# Driver_MOSFET_DC_Input.net
KiCad netlist of a schematic drawn in Altium Designer
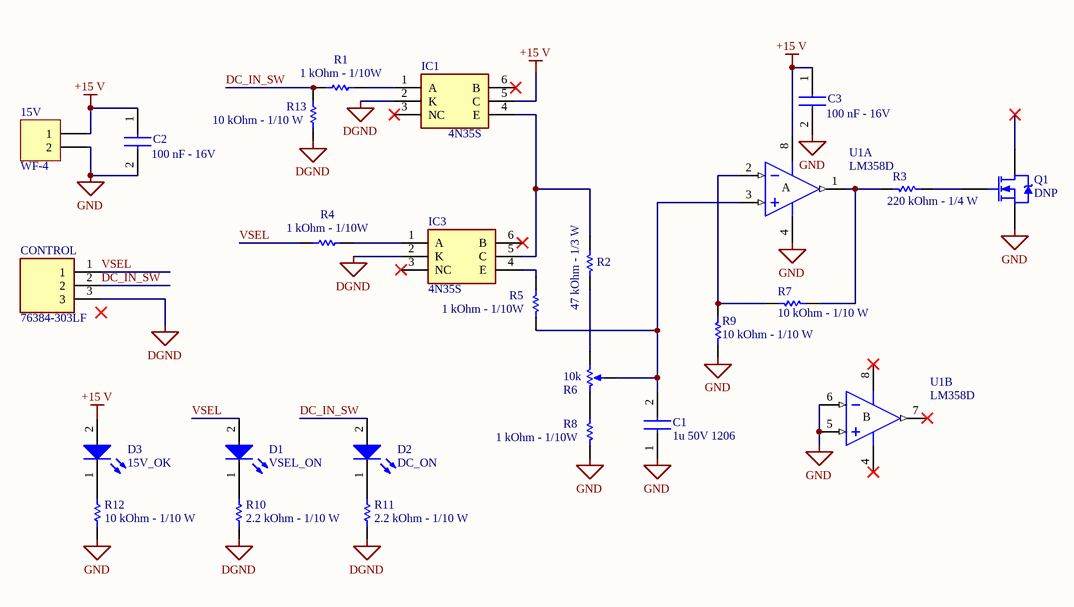
[diagram p0: Driver_MOSFET_DC_Input.SchDoc]

(export (version "E")
  (design (tool "Eeschema 10.0.6"))
  (components
    (comp (ref "15V")
      (value "WF-4")
      (footprint "HDR1X2")
      (description "Header, 2-Pin")
      (fields
        (field (name "MANUFACTURER_PART_NUMBER") "Header 2P")
        (field (name "PUBLISHER") "Altium Limited")
      )
      (libsource (lib "Miscellaneous Connectors") (part "MHDR1X2"))
    )
    (comp (ref "C1")
      (value "1u 50V 1206")
      (footprint "SamacSys:CAPC3216X180N")
      (description "Capacitor")
      (fields
        (field (name "MANUFACTURER_PART_NUMBER") "C3216X7R1H105K160AE")
        (field (name "MOUSER PART NUMBER") "810-C3216X7R1H105KST")
      )
      (libsource (lib "*") (part "C3216X7R1H105K160AE"))
    )
    (comp (ref "C2")
      (value "100 nF - 16V")
      (footprint "CAPC1608X95N")
      (description "Capacitor")
      (fields
        (field (name "MANUFACTURER_PART_NUMBER") "EMK107B7104KA-T")
        (field (name "MOUSER PART NUMBER") "963-EMK107B7104KA-T")
      )
      (libsource (lib "SamacSys") (part "EMK107B7104KA-T"))
    )
    (comp (ref "C3")
      (value "100 nF - 16V")
      (footprint "CAPC1608X95N")
      (description "Capacitor")
      (fields
        (field (name "MANUFACTURER_PART_NUMBER") "EMK107B7104KA-T")
        (field (name "MOUSER PART NUMBER") "963-EMK107B7104KA-T")
      )
      (libsource (lib "SamacSys") (part "EMK107B7104KA-T"))
    )
    (comp (ref "CONTROL")
      (value "76384-303LF")
      (footprint "76384303LF")
      (description "Connector")
      (fields (field (name "MOUSER PART NUMBER") "649-76384-303LF"))
      (libsource (lib "SamacSys") (part "76384-303LF"))
    )
    (comp (ref "D1")
      (value "VSEL_ON")
      (footprint "SamacSys:LEDC1608X80N")
      (description "LED")
      (fields
        (field (name "MANUFACTURER_PART_NUMBER") "150060GS75000")
        (field (name "MOUSER PART NUMBER") "710-150060GS75000")
      )
      (libsource (lib "SamacSys") (part "150060GS75000"))
    )
    (comp (ref "D2")
      (value "DC_ON")
      (footprint "SamacSys:LEDC1608X80N")
      (description "LED")
      (fields
        (field (name "MANUFACTURER_PART_NUMBER") "150060GS75000")
        (field (name "MOUSER PART NUMBER") "710-150060GS75000")
      )
      (libsource (lib "SamacSys") (part "150060GS75000"))
    )
    (comp (ref "D3")
      (value "15V_OK")
      (footprint "SamacSys:LEDC1608X80N")
      (description "LED")
      (fields
        (field (name "MANUFACTURER_PART_NUMBER") "150060GS75000")
        (field (name "MOUSER PART NUMBER") "710-150060GS75000")
      )
      (libsource (lib "SamacSys") (part "150060GS75000"))
    )
    (comp (ref "IC1")
      (value "4N35S")
      (footprint "SamacSys:4N35S")
      (description "Integrated Circuit")
      (libsource (lib "SamacSys") (part "4N35S"))
    )
    (comp (ref "IC3")
      (value "4N35S")
      (footprint "SamacSys:4N35S")
      (description "Integrated Circuit")
      (libsource (lib "SamacSys") (part "4N35S"))
    )
    (comp (ref "Q1")
      (value "DNP")
      (footprint "TO-247 Horiz. Heatsink")
      (description "Infineon Power MOSFET N-Channel 650V 31.2A")
      (fields (field (name "PUBLISHER") "Altium Limited"))
      (libsource (lib "MOSFET") (part "IPx65R110CFD"))
    )
    (comp (ref "R1")
      (value "1 kOhm - 1/10W")
      (footprint "SamacSys:RESC1608X55N")
      (description "Resistor")
      (fields (field (name "MANUFACTURER_PART_NUMBER") "RMC16K102FTP") (field (name "Comment") "1k"))
      (libsource (lib "SamacSys") (part "RMC16K102FTP"))
    )
    (comp (ref "R2")
      (value "47 kOhm - 1/3 W")
      (footprint "RESC1608X55N")
      (description "Resistor")
      (fields
        (field (name "MANUFACTURER_PART_NUMBER") "CRCW060347K0FKEAHP")
        (field (name "Comment") "Res1")
        (field (name "PUBLISHER") "Altium Limited")
      )
      (libsource (lib "Miscellaneous Devices") (part "Res1"))
    )
    (comp (ref "R3")
      (value "220 kOhm - 1/4 W")
      (footprint "RESC1608X55N")
      (description "Resistor")
      (fields
        (field (name "MANUFACTURER_PART_NUMBER") "CRCW1206220KFKEA")
        (field (name "Comment") "Res1")
        (field (name "PUBLISHER") "Altium Limited")
      )
      (libsource (lib "Miscellaneous Devices") (part "Res1"))
    )
    (comp (ref "R4")
      (value "1 kOhm - 1/10W")
      (footprint "SamacSys:RESC1608X55N")
      (description "Resistor")
      (fields (field (name "MANUFACTURER_PART_NUMBER") "RMC16K102FTP") (field (name "Comment") "1k"))
      (libsource (lib "SamacSys") (part "RMC16K102FTP"))
    )
    (comp (ref "R5")
      (value "1 kOhm - 1/10W")
      (footprint "RESC1608X55N")
      (description "Resistor")
      (fields
        (field (name "MANUFACTURER_PART_NUMBER") "RMC16K102FTP")
        (field (name "Comment") "Res1")
        (field (name "PUBLISHER") "Altium Limited")
      )
      (libsource (lib "Miscellaneous Devices") (part "Res1"))
    )
    (comp (ref "R6")
      (value "10k")
      (footprint "SamacSys:3296W-1")
      (description "Resistor")
      (fields
        (field (name "MANUFACTURER_PART_NUMBER") "3296W-1-502LF")
        (field (name "MOUSER PART NUMBER") "652-3296W-1-502LF")
      )
      (libsource (lib "SamacSys") (part "3296W-1-502LF"))
    )
    (comp (ref "R7")
      (value "10 kOhm - 1/10 W")
      (footprint "RESC1608X55N")
      (description "Resistor")
      (fields
        (field (name "MANUFACTURER_PART_NUMBER") "CRCW060310K0FKEA")
        (field (name "Comment") "Res1")
        (field (name "PUBLISHER") "Altium Limited")
      )
      (libsource (lib "Miscellaneous Devices") (part "Res1"))
    )
    (comp (ref "R8")
      (value "1 kOhm - 1/10W")
      (footprint "RESC1608X55N")
      (description "Resistor")
      (fields
        (field (name "MANUFACTURER_PART_NUMBER") "RMC16K102FTP")
        (field (name "Comment") "Res1")
        (field (name "PUBLISHER") "Altium Limited")
      )
      (libsource (lib "Miscellaneous Devices") (part "Res1"))
    )
    (comp (ref "R9")
      (value "10 kOhm - 1/10 W")
      (footprint "RESC1608X55N")
      (description "Resistor")
      (fields
        (field (name "MANUFACTURER_PART_NUMBER") "CRCW060310K0FKEA")
        (field (name "Comment") "Res1")
        (field (name "PUBLISHER") "Altium Limited")
      )
      (libsource (lib "Miscellaneous Devices") (part "Res1"))
    )
    (comp (ref "R10")
      (value "2.2 kOhm - 1/10 W")
      (footprint "RESC1608X50N")
      (description "Resistor")
      (fields
        (field (name "MANUFACTURER_PART_NUMBER") "CRCW06032K20FKEA")
        (field (name "MOUSER PART NUMBER") "71-CRCW0603-2.2K-E3")
      )
      (libsource (lib "SamacSys") (part "CRCW06032K20FKEA"))
    )
    (comp (ref "R11")
      (value "2.2 kOhm - 1/10 W")
      (footprint "RESC1608X50N")
      (description "Resistor")
      (fields
        (field (name "MANUFACTURER_PART_NUMBER") "CRCW06032K20FKEA")
        (field (name "MOUSER PART NUMBER") "71-CRCW0603-2.2K-E3")
      )
      (libsource (lib "SamacSys") (part "CRCW06032K20FKEA"))
    )
    (comp (ref "R12")
      (value "10 kOhm - 1/10 W")
      (footprint "RESC1608X50N")
      (description "Resistor")
      (fields
        (field (name "MANUFACTURER_PART_NUMBER") "CRCW060310K0FKEA")
        (field (name "MOUSER PART NUMBER") "71-CRCW0603-10K-E3")
      )
      (libsource (lib "SamacSys") (part "CRCW060310K0FKEA"))
    )
    (comp (ref "R13")
      (value "10 kOhm - 1/10 W")
      (footprint "RESC1608X50N")
      (description "Resistor")
      (fields
        (field (name "MANUFACTURER_PART_NUMBER") "CRCW060310K0FKEA")
        (field (name "MOUSER PART NUMBER") "71-CRCW0603-10K-E3")
      )
      (libsource (lib "SamacSys") (part "CRCW060310K0FKEA"))
    )
    (comp (ref "U1")
      (value "LM358D")
      (footprint "751-07_M")
      (description "Dual Operational Amplifier")
      (fields
        (field (name "MANUFACTURER_PART_NUMBER") "LM358AM/NOPB")
        (field (name "PUBLISHER") "Altium Limited")
      )
      (libsource (lib "TI Operational Amplifier") (part "LM358D"))
    )
  )
  (nets
    (net (code "1") (name "+15 V") (class "Default")
      (node (ref "15V") (pin "1") (pinfunction "1_1") (pintype "passive"))
      (node (ref "C2") (pin "1") (pinfunction "1_1") (pintype "passive"))
      (node (ref "C3") (pin "1") (pinfunction "1_1") (pintype "passive"))
      (node (ref "D3") (pin "2") (pinfunction "A_2") (pintype "passive"))
      (node (ref "IC1") (pin "5") (pinfunction "C_5") (pintype "passive"))
      (node (ref "U1") (pin "8") (pinfunction "V+_8") (pintype "power_in"))
    )
    (net (code "2") (name "/DC_IN_SW") (class "Default")
      (node (ref "CONTROL") (pin "2") (pinfunction "2_2") (pintype "passive"))
      (node (ref "D2") (pin "2") (pinfunction "A_2") (pintype "passive"))
      (node (ref "R1") (pin "1") (pinfunction "1_1") (pintype "passive"))
      (node (ref "R13") (pin "2") (pinfunction "2_2") (pintype "passive"))
    )
    (net (code "3") (name "/VSEL") (class "Default")
      (node (ref "CONTROL") (pin "1") (pinfunction "1_1") (pintype "passive"))
      (node (ref "D1") (pin "2") (pinfunction "A_2") (pintype "passive"))
      (node (ref "R4") (pin "1") (pinfunction "1_1") (pintype "passive"))
    )
    (net (code "4") (name "DGND") (class "Default")
      (node (ref "CONTROL") (pin "3") (pinfunction "3_3") (pintype "passive"))
      (node (ref "IC1") (pin "2") (pinfunction "K_2") (pintype "passive"))
      (node (ref "IC3") (pin "2") (pinfunction "K_2") (pintype "passive"))
      (node (ref "R10") (pin "1") (pinfunction "1_1") (pintype "passive"))
      (node (ref "R11") (pin "1") (pinfunction "1_1") (pintype "passive"))
      (node (ref "R13") (pin "1") (pinfunction "1_1") (pintype "passive"))
    )
    (net (code "5") (name "GND") (class "Default")
      (node (ref "15V") (pin "2") (pinfunction "2_2") (pintype "passive"))
      (node (ref "C1") (pin "1") (pinfunction "1_1") (pintype "passive"))
      (node (ref "C2") (pin "2") (pinfunction "2_2") (pintype "passive"))
      (node (ref "C3") (pin "2") (pinfunction "2_2") (pintype "passive"))
      (node (ref "Q1") (pin "3") (pinfunction "S_3") (pintype "passive"))
      (node (ref "R12") (pin "1") (pinfunction "1_1") (pintype "passive"))
      (node (ref "R8") (pin "2") (pinfunction "2_2") (pintype "passive"))
      (node (ref "R9") (pin "2") (pinfunction "2_2") (pintype "passive"))
      (node (ref "U1") (pin "4") (pinfunction "V-_4") (pintype "power_in"))
      (node (ref "U1") (pin "5") (pinfunction "IN+_5") (pintype "input"))
      (node (ref "U1") (pin "6") (pinfunction "IN-_6") (pintype "input"))
    )
    (net (code "6") (name "Net-(D1-K)") (class "Default")
      (node (ref "D1") (pin "1") (pinfunction "K_1") (pintype "passive"))
      (node (ref "R10") (pin "2") (pinfunction "2_2") (pintype "passive"))
    )
    (net (code "7") (name "Net-(D2-K)") (class "Default")
      (node (ref "D2") (pin "1") (pinfunction "K_1") (pintype "passive"))
      (node (ref "R11") (pin "2") (pinfunction "2_2") (pintype "passive"))
    )
    (net (code "8") (name "Net-(D3-K)") (class "Default")
      (node (ref "D3") (pin "1") (pinfunction "K_1") (pintype "passive"))
      (node (ref "R12") (pin "2") (pinfunction "2_2") (pintype "passive"))
    )
    (net (code "9") (name "Net-(IC1-A)") (class "Default")
      (node (ref "IC1") (pin "1") (pinfunction "A_1") (pintype "passive"))
      (node (ref "R1") (pin "2") (pinfunction "2_2") (pintype "passive"))
    )
    (net (code "10") (name "Net-(IC1-E)") (class "Default")
      (node (ref "IC1") (pin "4") (pinfunction "E_4") (pintype "passive"))
      (node (ref "IC3") (pin "5") (pinfunction "C_5") (pintype "passive"))
      (node (ref "R2") (pin "1") (pinfunction "1_1") (pintype "passive"))
    )
    (net (code "11") (name "Net-(IC3-A)") (class "Default")
      (node (ref "IC3") (pin "1") (pinfunction "A_1") (pintype "passive"))
      (node (ref "R4") (pin "2") (pinfunction "2_2") (pintype "passive"))
    )
    (net (code "12") (name "Net-(IC3-E)") (class "Default")
      (node (ref "IC3") (pin "4") (pinfunction "E_4") (pintype "passive"))
      (node (ref "R5") (pin "1") (pinfunction "1_1") (pintype "passive"))
    )
    (net (code "13") (name "Net-(Q1-G)") (class "Default")
      (node (ref "Q1") (pin "1") (pinfunction "G_1") (pintype "passive"))
      (node (ref "R3") (pin "2") (pinfunction "2_2") (pintype "passive"))
    )
    (net (code "14") (name "Net-(R6-BOT)") (class "Default")
      (node (ref "C1") (pin "2") (pinfunction "2_2") (pintype "passive"))
      (node (ref "R5") (pin "2") (pinfunction "2_2") (pintype "passive"))
      (node (ref "R6") (pin "2") (pinfunction "BOT_2") (pintype "passive"))
      (node (ref "U1") (pin "3") (pinfunction "IN+_3") (pintype "input"))
    )
    (net (code "15") (name "Net-(R6-TAP)") (class "Default")
      (node (ref "R6") (pin "3") (pinfunction "TAP_3") (pintype "passive"))
      (node (ref "R8") (pin "1") (pinfunction "1_1") (pintype "passive"))
    )
    (net (code "16") (name "Net-(R6-TOP)") (class "Default")
      (node (ref "R2") (pin "2") (pinfunction "2_2") (pintype "passive"))
      (node (ref "R6") (pin "1") (pinfunction "TOP_1") (pintype "passive"))
    )
    (net (code "17") (name "Net-(U1A-IN-)") (class "Default")
      (node (ref "R7") (pin "1") (pinfunction "1_1") (pintype "passive"))
      (node (ref "R9") (pin "1") (pinfunction "1_1") (pintype "passive"))
      (node (ref "U1") (pin "2") (pinfunction "IN-_2") (pintype "input"))
    )
    (net (code "18") (name "Net-(U1A-OUT)") (class "Default")
      (node (ref "R3") (pin "1") (pinfunction "1_1") (pintype "passive"))
      (node (ref "R7") (pin "2") (pinfunction "2_2") (pintype "passive"))
      (node (ref "U1") (pin "1") (pinfunction "OUT_1") (pintype "output"))
    )
    (net (code "19") (name "unconnected-(IC1-B-Pad6)") (class "Default")
      (node (ref "IC1") (pin "6") (pinfunction "B_6") (pintype "passive+no_connect"))
    )
    (net (code "20") (name "unconnected-(IC1-NC-Pad3)") (class "Default")
      (node (ref "IC1") (pin "3") (pinfunction "NC_3") (pintype "passive+no_connect"))
    )
    (net (code "21") (name "unconnected-(IC3-B-Pad6)") (class "Default")
      (node (ref "IC3") (pin "6") (pinfunction "B_6") (pintype "passive+no_connect"))
    )
    (net (code "22") (name "unconnected-(IC3-NC-Pad3)") (class "Default")
      (node (ref "IC3") (pin "3") (pinfunction "NC_3") (pintype "passive+no_connect"))
    )
    (net (code "23") (name "unconnected-(Q1-D-Pad2)") (class "Default")
      (node (ref "Q1") (pin "2") (pinfunction "D_2") (pintype "passive+no_connect"))
    )
    (net (code "24") (name "unconnected-(U1B-OUT-Pad7)") (class "Default")
      (node (ref "U1") (pin "7") (pinfunction "OUT_7") (pintype "output+no_connect"))
    )
    (net (code "25") (name "unconnected-(U1B-V+-Pad8)") (class "Default")
      (node (ref "U1") (pin "8") (pinfunction "V+_8") (pintype "power_in+no_connect"))
    )
    (net (code "26") (name "unconnected-(U1B-V--Pad4)") (class "Default")
      (node (ref "U1") (pin "4") (pinfunction "V-_4") (pintype "power_in+no_connect"))
    )
  )
)
